# quadrotor_100N_Sheet1.net
KiCad netlist of a schematic drawn in Altium Designer
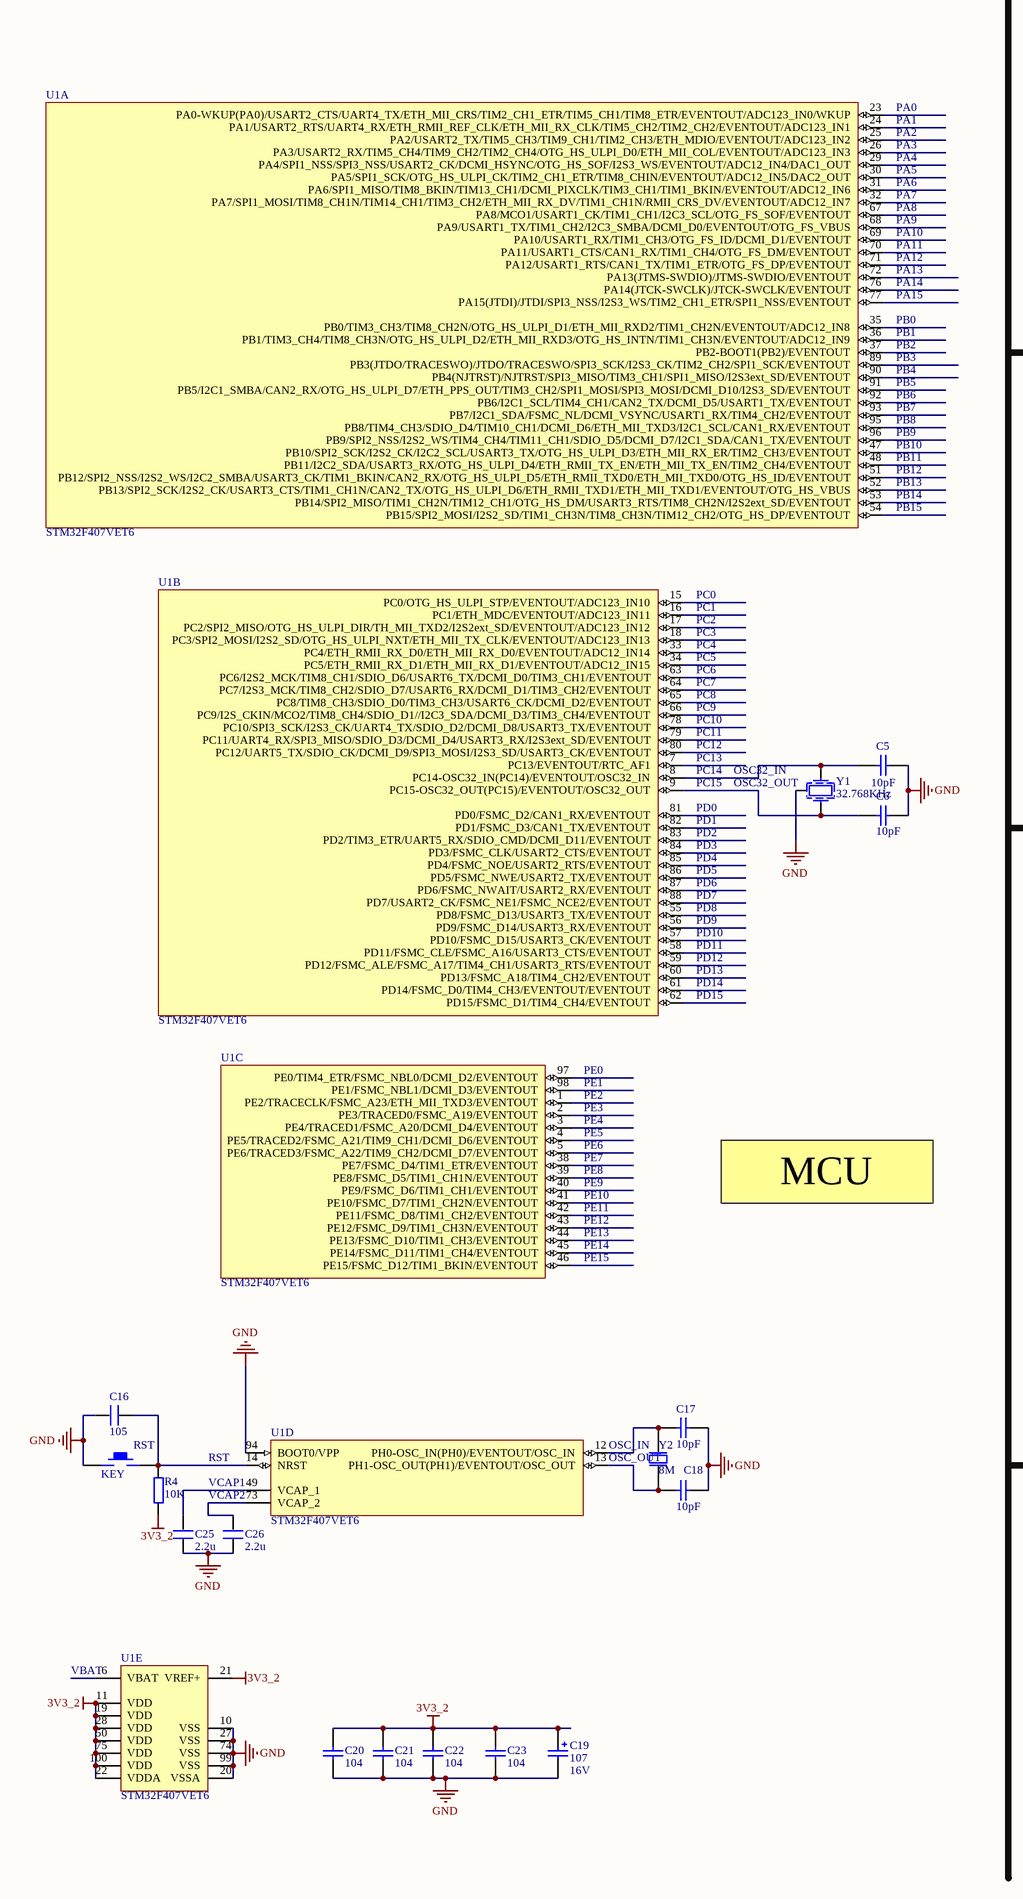
[diagram p0: quadrotor_100N_Sheet1.SchDoc, left]
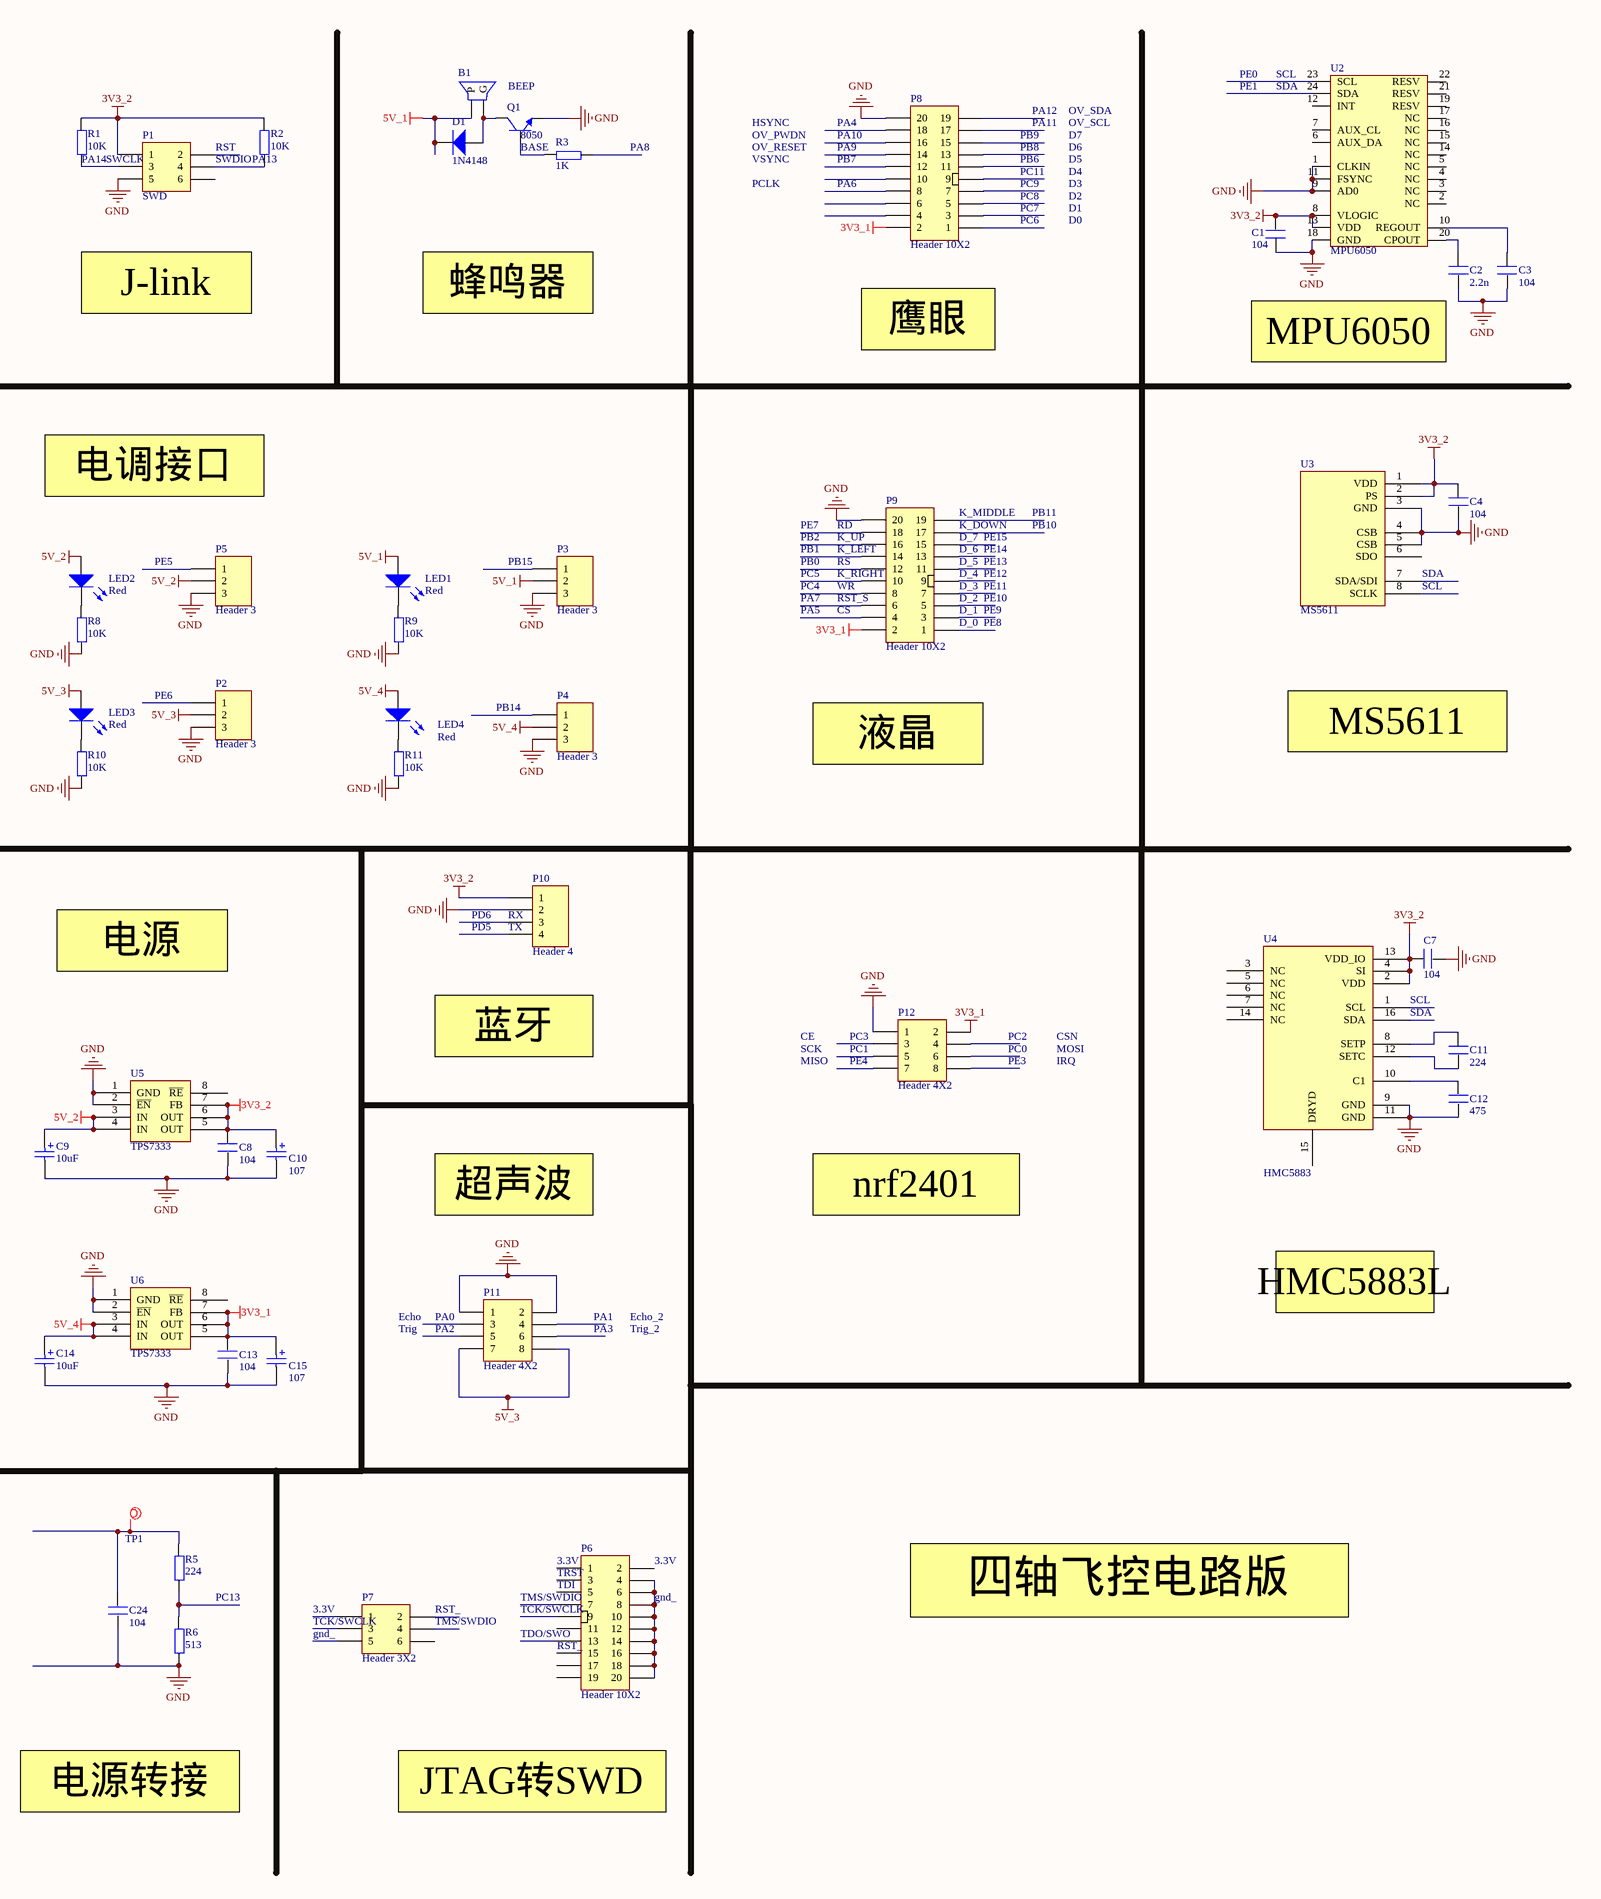
[diagram p1: quadrotor_100N_Sheet1.SchDoc, right]

(export (version "E")
  (design (tool "Eeschema 10.0.6"))
  (components
    (comp (ref "B1") (value "BEEP") (footprint "BEEP") (libsource (lib "电磁组") (part "BEEP")))
    (comp (ref "C1") (value "104") (footprint "C0805") (libsource (lib "WARSHIP") (part "C")))
    (comp (ref "C2") (value "2.2n") (footprint "C0805") (libsource (lib "WARSHIP") (part "C")))
    (comp (ref "C3") (value "104") (footprint "C0805") (libsource (lib "WARSHIP") (part "C")))
    (comp (ref "C4") (value "104") (footprint "C0805") (libsource (lib "WARSHIP") (part "C")))
    (comp (ref "C5")
      (value "10pF")
      (footprint "CAPC2012[0805]")
      (description "Chip Capacitor, PSpice Model")
      (fields
        (field (name "TOLERANCE") "Y5V")
        (field (name "VOLTAGE") "63V")
        (field (name "PUBLISHER") "Altium Limited")
      )
      (libsource (lib "!)Miscellaneous Integrated Library") (part "Cap Chip 1"))
    )
    (comp (ref "C6")
      (value "10pF")
      (footprint "CAPC2012[0805]")
      (description "Chip Capacitor, PSpice Model")
      (fields
        (field (name "TOLERANCE") "Y5V")
        (field (name "VOLTAGE") "63V")
        (field (name "PUBLISHER") "Altium Limited")
      )
      (libsource (lib "!)Miscellaneous Integrated Library") (part "Cap Chip 1"))
    )
    (comp (ref "C7") (value "104") (footprint "C0805") (libsource (lib "WARSHIP") (part "C")))
    (comp (ref "C8") (value "104") (footprint "C0805") (libsource (lib "WARSHIP") (part "C")))
    (comp (ref "C9")
      (value "10uF")
      (footprint "CAPS8")
      (description "Polarized Capacitor (Radial)")
      (fields (field (name "VOLTAGE") "16V") (field (name "PUBLISHER") "Altium Limited"))
      (libsource (lib "!)Miscellaneous Integrated Library") (part "Cap Solid"))
    )
    (comp (ref "C10")
      (value "107")
      (footprint "CAPT6032")
      (description "Molded (Tantalum) Capacitor, 2-Leads,")
      (fields (field (name "VOLTAGE") "16V") (field (name "PUBLISHER") "Altium Limited"))
      (libsource (lib "!)Miscellaneous Integrated Library") (part "Cap Tan"))
    )
    (comp (ref "C11") (value "224") (footprint "C0805") (libsource (lib "WARSHIP") (part "C")))
    (comp (ref "C12") (value "475") (footprint "C0805") (libsource (lib "WARSHIP") (part "C")))
    (comp (ref "C13") (value "104") (footprint "C0805") (libsource (lib "WARSHIP") (part "C")))
    (comp (ref "C14")
      (value "10uF")
      (footprint "CAPS8")
      (description "Polarized Capacitor (Radial)")
      (fields (field (name "VOLTAGE") "16V") (field (name "PUBLISHER") "Altium Limited"))
      (libsource (lib "!)Miscellaneous Integrated Library") (part "Cap Solid"))
    )
    (comp (ref "C15")
      (value "107")
      (footprint "CAPT6032")
      (description "Molded (Tantalum) Capacitor, 2-Leads,")
      (fields (field (name "VOLTAGE") "16V") (field (name "PUBLISHER") "Altium Limited"))
      (libsource (lib "!)Miscellaneous Integrated Library") (part "Cap Tan"))
    )
    (comp (ref "C16") (value "105") (footprint "C0805") (libsource (lib "WARSHIP") (part "C")))
    (comp (ref "C17")
      (value "10pF")
      (footprint "CAPC2012[0805]")
      (description "Chip Capacitor, PSpice Model")
      (fields
        (field (name "TOLERANCE") "Y5V")
        (field (name "VOLTAGE") "63V")
        (field (name "PUBLISHER") "Altium Limited")
      )
      (libsource (lib "!)Miscellaneous Integrated Library") (part "Cap Chip 1"))
    )
    (comp (ref "C18")
      (value "10pF")
      (footprint "CAPC2012[0805]")
      (description "Chip Capacitor, PSpice Model")
      (fields
        (field (name "TOLERANCE") "Y5V")
        (field (name "VOLTAGE") "63V")
        (field (name "PUBLISHER") "Altium Limited")
      )
      (libsource (lib "!)Miscellaneous Integrated Library") (part "Cap Chip 1"))
    )
    (comp (ref "C19")
      (value "107")
      (footprint "CAPT6032")
      (description "Molded (Tantalum) Capacitor, 2-Leads,")
      (fields (field (name "VOLTAGE") "16V") (field (name "PUBLISHER") "Altium Limited"))
      (libsource (lib "!)Miscellaneous Integrated Library") (part "Cap Tan"))
    )
    (comp (ref "C20")
      (value "104")
      (footprint "CAPC2012[0805]")
      (description "Chip Capacitor, PSpice Model")
      (fields
        (field (name "TOLERANCE") "Y5V")
        (field (name "VOLTAGE") "63V")
        (field (name "PUBLISHER") "Altium Limited")
      )
      (libsource (lib "!)Miscellaneous Integrated Library") (part "Cap Chip 1"))
    )
    (comp (ref "C21")
      (value "104")
      (footprint "CAPC2012[0805]")
      (description "Chip Capacitor, PSpice Model")
      (fields
        (field (name "TOLERANCE") "Y5V")
        (field (name "VOLTAGE") "63V")
        (field (name "PUBLISHER") "Altium Limited")
      )
      (libsource (lib "!)Miscellaneous Integrated Library") (part "Cap Chip 1"))
    )
    (comp (ref "C22")
      (value "104")
      (footprint "CAPC2012[0805]")
      (description "Chip Capacitor, PSpice Model")
      (fields
        (field (name "TOLERANCE") "Y5V")
        (field (name "VOLTAGE") "63V")
        (field (name "PUBLISHER") "Altium Limited")
      )
      (libsource (lib "!)Miscellaneous Integrated Library") (part "Cap Chip 1"))
    )
    (comp (ref "C23")
      (value "104")
      (footprint "CAPC2012[0805]")
      (description "Chip Capacitor, PSpice Model")
      (fields
        (field (name "TOLERANCE") "Y5V")
        (field (name "VOLTAGE") "63V")
        (field (name "PUBLISHER") "Altium Limited")
      )
      (libsource (lib "!)Miscellaneous Integrated Library") (part "Cap Chip 1"))
    )
    (comp (ref "C24") (value "104") (footprint "0805C") (libsource (lib "WARSHIP") (part "C")))
    (comp (ref "C25") (value "2.2u") (footprint "C0805") (libsource (lib "WARSHIP") (part "C")))
    (comp (ref "C26") (value "2.2u") (footprint "C0805") (libsource (lib "WARSHIP") (part "C")))
    (comp (ref "D1")
      (value "1N4148")
      (footprint "SOD-80[LL-34]")
      (description "SMT Glass Diode, PSpice Model")
      (fields (field (name "PARTNUMBER") "1N4148") (field (name "PUBLISHER") "Altium Limited"))
      (libsource (lib "!)Miscellaneous Integrated Library") (part "Diode 1N4148"))
    )
    (comp (ref "LED1")
      (value "Red")
      (footprint "LEDC2012(0805)")
      (description "Typical Chip LED")
      (fields (field (name "COLOR") "Red") (field (name "PUBLISHER") "Altium Limited"))
      (libsource (lib "!)Miscellaneous Integrated Library") (part "LED Chip"))
    )
    (comp (ref "LED2")
      (value "Red")
      (footprint "LEDC2012(0805)")
      (description "Typical Chip LED")
      (fields (field (name "COLOR") "Red") (field (name "PUBLISHER") "Altium Limited"))
      (libsource (lib "!)Miscellaneous Integrated Library") (part "LED Chip"))
    )
    (comp (ref "LED3")
      (value "Red")
      (footprint "LEDC2012(0805)")
      (description "Typical Chip LED")
      (fields (field (name "COLOR") "Red") (field (name "PUBLISHER") "Altium Limited"))
      (libsource (lib "!)Miscellaneous Integrated Library") (part "LED Chip"))
    )
    (comp (ref "LED4")
      (value "Red")
      (footprint "LEDC2012(0805)")
      (description "Typical Chip LED")
      (fields (field (name "COLOR") "Red") (field (name "PUBLISHER") "Altium Limited"))
      (libsource (lib "!)Miscellaneous Integrated Library") (part "LED Chip"))
    )
    (comp (ref "P1")
      (value "SWD")
      (footprint "HDR2X3")
      (description "Header, 3-Pin, Dual row")
      (fields (field (name "PUBLISHER") "Altium Limited"))
      (libsource (lib "!)Miscellaneous Integrated Library") (part "Header 3X2"))
    )
    (comp (ref "P2")
      (value "Header 3")
      (footprint "HDR1X3")
      (description "Header, 3-Pin")
      (fields (field (name "PUBLISHER") "Altium Limited"))
      (libsource (lib "!)Miscellaneous Integrated Library") (part "Header 3"))
    )
    (comp (ref "P3")
      (value "Header 3")
      (footprint "HDR1X3")
      (description "Header, 3-Pin")
      (fields (field (name "PUBLISHER") "Altium Limited"))
      (libsource (lib "!)Miscellaneous Integrated Library") (part "Header 3"))
    )
    (comp (ref "P4")
      (value "Header 3")
      (footprint "HDR1X3")
      (description "Header, 3-Pin")
      (fields (field (name "PUBLISHER") "Altium Limited"))
      (libsource (lib "!)Miscellaneous Integrated Library") (part "Header 3"))
    )
    (comp (ref "P5")
      (value "Header 3")
      (footprint "HDR1X3")
      (description "Header, 3-Pin")
      (fields (field (name "PUBLISHER") "Altium Limited"))
      (libsource (lib "!)Miscellaneous Integrated Library") (part "Header 3"))
    )
    (comp (ref "P6")
      (value "Header 10X2")
      (footprint "IDC2.54-20")
      (description "Header, 10-Pin, Dual row")
      (fields (field (name "PUBLISHER") "Altium Limited"))
      (libsource (lib "") (part "Header 10X2_1"))
    )
    (comp (ref "P7")
      (value "Header 3X2")
      (footprint "HDR2X3")
      (description "Header, 3-Pin, Dual row")
      (fields (field (name "PUBLISHER") "Altium Limited"))
      (libsource (lib "!)Miscellaneous Integrated Library") (part "Header 3X2"))
    )
    (comp (ref "P8")
      (value "Header 10X2")
      (footprint "HDR2X10")
      (description "Header, 10-Pin, Dual row")
      (fields (field (name "PUBLISHER") "Altium Limited"))
      (libsource (lib "!)Miscellaneous Integrated Library") (part "Header 10X2"))
    )
    (comp (ref "P9")
      (value "Header 10X2")
      (footprint "HDR2X10")
      (description "Header, 10-Pin, Dual row")
      (fields (field (name "PUBLISHER") "Altium Limited"))
      (libsource (lib "!)Miscellaneous Integrated Library") (part "Header 10X2"))
    )
    (comp (ref "P10")
      (value "Header 4")
      (footprint "HX2.54V-4")
      (description "Header, 4-Pin")
      (fields (field (name "PUBLISHER") "Altium Limited"))
      (libsource (lib "!)Miscellaneous Integrated Library") (part "Header 4"))
    )
    (comp (ref "P11")
      (value "Header 4X2")
      (footprint "HDR2X4")
      (description "Header, 4-Pin, Dual row")
      (fields (field (name "PUBLISHER") "Altium Limited"))
      (libsource (lib "!)Miscellaneous Integrated Library") (part "Header 4X2"))
    )
    (comp (ref "P12")
      (value "Header 4X2")
      (footprint "HDR2X4")
      (description "Header, 4-Pin, Dual row")
      (fields (field (name "PUBLISHER") "Altium Limited"))
      (libsource (lib "!)Miscellaneous Integrated Library") (part "Header 4X2"))
    )
    (comp (ref "Q1")
      (value "8050")
      (footprint "SOT23")
      (description "NPN Bipolar Transistor")
      (fields (field (name "PARTNUMBER") "8050") (field (name "PUBLISHER") "Altium Limited"))
      (libsource (lib "!)Miscellaneous Integrated Library") (part "NPN BC817-40"))
    )
    (comp (ref "R1") (value "10K") (footprint "0805") (libsource (lib "WARSHIP") (part "R")))
    (comp (ref "R2") (value "10K") (footprint "0805") (libsource (lib "WARSHIP") (part "R")))
    (comp (ref "R3") (value "1K") (footprint "0805") (libsource (lib "WARSHIP") (part "R")))
    (comp (ref "R4") (value "10K") (footprint "0805") (libsource (lib "WARSHIP") (part "R")))
    (comp (ref "R5") (value "224") (footprint "0805R") (libsource (lib "WARSHIP") (part "R")))
    (comp (ref "R6") (value "513") (footprint "0805R") (libsource (lib "WARSHIP") (part "R")))
    (comp (ref "R8") (value "10K") (footprint "0805") (libsource (lib "WARSHIP") (part "R")))
    (comp (ref "R9") (value "10K") (footprint "0805") (libsource (lib "WARSHIP") (part "R")))
    (comp (ref "R10") (value "10K") (footprint "0805") (libsource (lib "WARSHIP") (part "R")))
    (comp (ref "R11") (value "10K") (footprint "0805") (libsource (lib "WARSHIP") (part "R")))
    (comp (ref "RST") (value "KEY") (footprint "KEY") (libsource (lib "电磁组") (part "KEY")))
    (comp (ref "TP1")
      (value "Test Point")
      (footprint "TESTPOINT_PAD_3")
      (description "Test Point for Manufature")
      (libsource (lib "!)Miscellaneous Integrated Library") (part "Test Point"))
    )
    (comp (ref "U1")
      (value "STM32F407VET6")
      (footprint "LQFP100_M")
      (libsource (lib "STMicroelectronics STM32 F4") (part "STM32F407VET6"))
    )
    (comp (ref "U2")
      (value "MPU6050")
      (footprint "QFN24")
      (description "9轴运动处理传感器")
      (libsource (lib "ATK-MPU6050六轴传感器模块") (part "MPU6050"))
    )
    (comp (ref "U3") (value "MS5611") (footprint "MS5611") (libsource (lib "电磁组") (part "MS5611")))
    (comp (ref "U4") (value "HMC5883") (footprint "QFN16") (libsource (lib "电磁组") (part "HMC5883")))
    (comp (ref "U5") (value "TPS7333") (footprint "TPS7333") (libsource (lib "Schlib1") (part "TPS7333")))
    (comp (ref "U6") (value "TPS7333") (footprint "TPS7333") (libsource (lib "Schlib1") (part "TPS7333")))
    (comp (ref "Y1")
      (value "32.768KHz")
      (footprint "XTAL")
      (description "3-pin Crystal Oscillator, Case Shelter")
      (libsource (lib "!)Miscellaneous Integrated Library") (part "XTAL 3P"))
    )
    (comp (ref "Y2")
      (value "8M")
      (footprint "XTAL-SMD")
      (description "Crystal Oscillator")
      (fields (field (name "PUBLISHER") "Altium Limited"))
      (libsource (lib "!)Miscellaneous Integrated Library") (part "XTAL"))
    )
  )
  (nets
    (net (code "1") (name "/3.3V") (class "Default")
      (node (ref "P6") (pin "1") (pinfunction "1_1") (pintype "passive"))
      (node (ref "P6") (pin "2") (pinfunction "2_2") (pintype "passive"))
      (node (ref "P7") (pin "1") (pinfunction "1_1") (pintype "passive"))
    )
    (net (code "2") (name "/BASE") (class "Default")
      (node (ref "Q1") (pin "1") (pinfunction "B_1") (pintype "passive"))
      (node (ref "R3") (pin "1") (pintype "passive"))
    )
    (net (code "4") (name "/CS") (class "Default")
      (node (ref "P9") (pin "4") (pinfunction "4_4") (pintype "passive"))
      (node (ref "U1") (pin "30") (pinfunction "PA5/SPI1_SCK/OTG_HS_ULPI_CK/TIM2_CH1_ETR/TIM8_CHIN/EVENTOUT/ADC12_IN5/DAC2_OUT_30") (pintype "bidirectional"))
    )
    (net (code "14") (name "/D_0") (class "Default")
      (node (ref "P9") (pin "1") (pinfunction "1_1") (pintype "passive"))
      (node (ref "U1") (pin "39") (pinfunction "PE8/FSMC_D5/TIM1_CH1N/EVENTOUT_39") (pintype "bidirectional"))
    )
    (net (code "15") (name "/D_1") (class "Default")
      (node (ref "P9") (pin "3") (pinfunction "3_3") (pintype "passive"))
      (node (ref "U1") (pin "40") (pinfunction "PE9/FSMC_D6/TIM1_CH1/EVENTOUT_40") (pintype "bidirectional"))
    )
    (net (code "16") (name "/D_2") (class "Default")
      (node (ref "P9") (pin "5") (pinfunction "5_5") (pintype "passive"))
      (node (ref "U1") (pin "41") (pinfunction "PE10/FSMC_D7/TIM1_CH2N/EVENTOUT_41") (pintype "bidirectional"))
    )
    (net (code "17") (name "/D_3") (class "Default")
      (node (ref "P9") (pin "7") (pinfunction "7_7") (pintype "passive"))
      (node (ref "U1") (pin "42") (pinfunction "PE11/FSMC_D8/TIM1_CH2/EVENTOUT_42") (pintype "bidirectional"))
    )
    (net (code "18") (name "/D_4") (class "Default")
      (node (ref "P9") (pin "9") (pinfunction "9_9") (pintype "passive"))
      (node (ref "U1") (pin "43") (pinfunction "PE12/FSMC_D9/TIM1_CH3N/EVENTOUT_43") (pintype "bidirectional"))
    )
    (net (code "19") (name "/D_5") (class "Default")
      (node (ref "P9") (pin "11") (pinfunction "11_11") (pintype "passive"))
      (node (ref "U1") (pin "44") (pinfunction "PE13/FSMC_D10/TIM1_CH3/EVENTOUT_44") (pintype "bidirectional"))
    )
    (net (code "20") (name "/D_6") (class "Default")
      (node (ref "P9") (pin "13") (pinfunction "13_13") (pintype "passive"))
      (node (ref "U1") (pin "45") (pinfunction "PE14/FSMC_D11/TIM1_CH4/EVENTOUT_45") (pintype "bidirectional"))
    )
    (net (code "21") (name "/D_7") (class "Default")
      (node (ref "P9") (pin "15") (pinfunction "15_15") (pintype "passive"))
      (node (ref "U1") (pin "46") (pinfunction "PE15/FSMC_D12/TIM1_BKIN/EVENTOUT_46") (pintype "bidirectional"))
    )
    (net (code "26") (name "/K_DOWN") (class "Default")
      (node (ref "P9") (pin "17") (pinfunction "17_17") (pintype "passive"))
      (node (ref "U1") (pin "47") (pinfunction "PB10/SPI2_SCK/I2S2_CK/I2C2_SCL/USART3_TX/OTG_HS_ULPI_D3/ETH_MII_RX_ER/TIM2_CH3/EVENTOUT_47") (pintype "bidirectional"))
    )
    (net (code "27") (name "/K_LEFT") (class "Default")
      (node (ref "P9") (pin "14") (pinfunction "14_14") (pintype "passive"))
      (node (ref "U1") (pin "36") (pinfunction "PB1/TIM3_CH4/TIM8_CH3N/OTG_HS_ULPI_D2/ETH_MII_RXD3/OTG_HS_INTN/TIM1_CH3N/EVENTOUT/ADC12_IN9_36") (pintype "bidirectional"))
    )
    (net (code "28") (name "/K_MIDDLE") (class "Default")
      (node (ref "P9") (pin "19") (pinfunction "19_19") (pintype "passive"))
      (node (ref "U1") (pin "48") (pinfunction "PB11/I2C2_SDA/USART3_RX/OTG_HS_ULPI_D4/ETH_RMII_TX_EN/ETH_MII_TX_EN/TIM2_CH4/EVENTOUT_48") (pintype "bidirectional"))
    )
    (net (code "29") (name "/K_RIGHT") (class "Default")
      (node (ref "P9") (pin "10") (pinfunction "10_10") (pintype "passive"))
      (node (ref "U1") (pin "34") (pinfunction "PC5/ETH_RMII_RX_D1/ETH_MII_RX_D1/EVENTOUT/ADC12_IN15_34") (pintype "bidirectional"))
    )
    (net (code "30") (name "/K_UP") (class "Default")
      (node (ref "P9") (pin "16") (pinfunction "16_16") (pintype "passive"))
      (node (ref "U1") (pin "37") (pinfunction "PB2-BOOT1(PB2)/EVENTOUT_37") (pintype "bidirectional"))
    )
    (net (code "33") (name "/OSC32_IN") (class "Default")
      (node (ref "C5") (pin "1") (pinfunction "1_1") (pintype "passive"))
      (node (ref "U1") (pin "8") (pinfunction "PC14-OSC32_IN(PC14)/EVENTOUT/OSC32_IN_8") (pintype "bidirectional"))
      (node (ref "Y1") (pin "1") (pintype "passive"))
    )
    (net (code "34") (name "/OSC32_OUT") (class "Default")
      (node (ref "C6") (pin "1") (pinfunction "1_1") (pintype "passive"))
      (node (ref "U1") (pin "9") (pinfunction "PC15-OSC32_OUT(PC15)/EVENTOUT/OSC32_OUT_9") (pintype "bidirectional"))
      (node (ref "Y1") (pin "2") (pintype "passive"))
    )
    (net (code "35") (name "/OSC_IN") (class "Default")
      (node (ref "C17") (pin "1") (pinfunction "1_1") (pintype "passive"))
      (node (ref "U1") (pin "12") (pinfunction "PH0-OSC_IN(PH0)/EVENTOUT/OSC_IN_12") (pintype "bidirectional"))
      (node (ref "Y2") (pin "2") (pinfunction "OSC2_2") (pintype "passive"))
    )
    (net (code "36") (name "/OSC_OUT") (class "Default")
      (node (ref "C18") (pin "1") (pinfunction "1_1") (pintype "passive"))
      (node (ref "U1") (pin "13") (pinfunction "PH1-OSC_OUT(PH1)/EVENTOUT/OSC_OUT_13") (pintype "bidirectional"))
      (node (ref "Y2") (pin "1") (pinfunction "OSC1_1") (pintype "passive"))
    )
    (net (code "41") (name "/PA0") (class "Default")
      (node (ref "P11") (pin "3") (pinfunction "3_3") (pintype "passive"))
      (node (ref "U1") (pin "23") (pinfunction "PA0-WKUP(PA0)/USART2_CTS/UART4_TX/ETH_MII_CRS/TIM2_CH1_ETR/TIM5_CH1/TIM8_ETR/EVENTOUT/ADC123_IN0/WKUP_23") (pintype "bidirectional"))
    )
    (net (code "42") (name "/PA1") (class "Default")
      (node (ref "P11") (pin "4") (pinfunction "4_4") (pintype "passive"))
      (node (ref "U1") (pin "24") (pinfunction "PA1/USART2_RTS/UART4_RX/ETH_RMII_REF_CLK/ETH_MII_RX_CLK/TIM5_CH2/TIM2_CH2/EVENTOUT/ADC123_IN1_24") (pintype "bidirectional"))
    )
    (net (code "43") (name "/PA2") (class "Default")
      (node (ref "P11") (pin "5") (pinfunction "5_5") (pintype "passive"))
      (node (ref "U1") (pin "25") (pinfunction "PA2/USART2_TX/TIM5_CH3/TIM9_CH1/TIM2_CH3/ETH_MDIO/EVENTOUT/ADC123_IN2_25") (pintype "bidirectional"))
    )
    (net (code "44") (name "/PA3") (class "Default")
      (node (ref "P11") (pin "6") (pinfunction "6_6") (pintype "passive"))
      (node (ref "U1") (pin "26") (pinfunction "PA3/USART2_RX/TIM5_CH4/TIM9_CH2/TIM2_CH4/OTG_HS_ULPI_D0/ETH_MII_COL/EVENTOUT/ADC123_IN3_26") (pintype "bidirectional"))
    )
    (net (code "45") (name "/PA4") (class "Default")
      (node (ref "P8") (pin "18") (pinfunction "18_18") (pintype "passive"))
      (node (ref "U1") (pin "29") (pinfunction "PA4/SPI1_NSS/SPI3_NSS/USART2_CK/DCMI_HSYNC/OTG_HS_SOF/I2S3_WS/EVENTOUT/ADC12_IN4/DAC1_OUT_29") (pintype "bidirectional"))
    )
    (net (code "46") (name "/PA6") (class "Default")
      (node (ref "P8") (pin "8") (pinfunction "8_8") (pintype "passive"))
      (node (ref "U1") (pin "31") (pinfunction "PA6/SPI1_MISO/TIM8_BKIN/TIM13_CH1/DCMI_PIXCLK/TIM3_CH1/TIM1_BKIN/EVENTOUT/ADC12_IN6_31") (pintype "bidirectional"))
    )
    (net (code "47") (name "/PA7") (class "Default")
      (node (ref "P9") (pin "6") (pinfunction "6_6") (pintype "passive"))
      (node (ref "U1") (pin "32") (pinfunction "PA7/SPI1_MOSI/TIM8_CH1N/TIM14_CH1/TIM3_CH2/ETH_MII_RX_DV/TIM1_CH1N/RMII_CRS_DV/EVENTOUT/ADC12_IN7_32") (pintype "bidirectional"))
    )
    (net (code "48") (name "/PA8") (class "Default")
      (node (ref "R3") (pin "2") (pintype "passive"))
      (node (ref "U1") (pin "67") (pinfunction "PA8/MCO1/USART1_CK/TIM1_CH1/I2C3_SCL/OTG_FS_SOF/EVENTOUT_67") (pintype "bidirectional"))
    )
    (net (code "49") (name "/PA9") (class "Default")
      (node (ref "P8") (pin "14") (pinfunction "14_14") (pintype "passive"))
      (node (ref "U1") (pin "68") (pinfunction "PA9/USART1_TX/TIM1_CH2/I2C3_SMBA/DCMI_D0/EVENTOUT/OTG_FS_VBUS_68") (pintype "bidirectional"))
    )
    (net (code "50") (name "/PA10") (class "Default")
      (node (ref "P8") (pin "16") (pinfunction "16_16") (pintype "passive"))
      (node (ref "U1") (pin "69") (pinfunction "PA10/USART1_RX/TIM1_CH3/OTG_FS_ID/DCMI_D1/EVENTOUT_69") (pintype "bidirectional"))
    )
    (net (code "51") (name "/PA11") (class "Default")
      (node (ref "P8") (pin "17") (pinfunction "17_17") (pintype "passive"))
      (node (ref "U1") (pin "70") (pinfunction "PA11/USART1_CTS/CAN1_RX/TIM1_CH4/OTG_FS_DM/EVENTOUT_70") (pintype "bidirectional"))
    )
    (net (code "52") (name "/PA12") (class "Default")
      (node (ref "P8") (pin "19") (pinfunction "19_19") (pintype "passive"))
      (node (ref "U1") (pin "71") (pinfunction "PA12/USART1_RTS/CAN1_TX/TIM1_ETR/OTG_FS_DP/EVENTOUT_71") (pintype "bidirectional"))
    )
    (net (code "53") (name "/PA13") (class "Default")
      (node (ref "P1") (pin "4") (pinfunction "4_4") (pintype "passive"))
      (node (ref "R2") (pin "1") (pintype "passive"))
      (node (ref "U1") (pin "72") (pinfunction "PA13(JTMS-SWDIO)/JTMS-SWDIO/EVENTOUT_72") (pintype "bidirectional"))
    )
    (net (code "54") (name "/PA14") (class "Default")
      (node (ref "P1") (pin "3") (pinfunction "3_3") (pintype "passive"))
      (node (ref "R1") (pin "1") (pintype "passive"))
      (node (ref "U1") (pin "76") (pinfunction "PA14(JTCK-SWCLK)/JTCK-SWCLK/EVENTOUT_76") (pintype "bidirectional"))
    )
    (net (code "55") (name "/PA15") (class "Default")
      (node (ref "U1") (pin "77") (pinfunction "PA15(JTDI)/JTDI/SPI3_NSS/I2S3_WS/TIM2_CH1_ETR/SPI1_NSS/EVENTOUT_77") (pintype "bidirectional"))
    )
    (net (code "56") (name "/PB0") (class "Default")
      (node (ref "P9") (pin "12") (pinfunction "12_12") (pintype "passive"))
      (node (ref "U1") (pin "35") (pinfunction "PB0/TIM3_CH3/TIM8_CH2N/OTG_HS_ULPI_D1/ETH_MII_RXD2/TIM1_CH2N/EVENTOUT/ADC12_IN8_35") (pintype "bidirectional"))
    )
    (net (code "57") (name "/PB3") (class "Default")
      (node (ref "U1") (pin "89") (pinfunction "PB3(JTDO/TRACESWO)/JTDO/TRACESWO/SPI3_SCK/I2S3_CK/TIM2_CH2/SPI1_SCK/EVENTOUT_89") (pintype "bidirectional"))
    )
    (net (code "58") (name "/PB4") (class "Default")
      (node (ref "U1") (pin "90") (pinfunction "PB4(NJTRST)/NJTRST/SPI3_MISO/TIM3_CH1/SPI1_MISO/I2S3ext_SD/EVENTOUT_90") (pintype "bidirectional"))
    )
    (net (code "59") (name "/PB5") (class "Default")
      (node (ref "U1") (pin "91") (pinfunction "PB5/I2C1_SMBA/CAN2_RX/OTG_HS_ULPI_D7/ETH_PPS_OUT/TIM3_CH2/SPI1_MOSI/SPI3_MOSI/DCMI_D10/I2S3_SD/EVENTOUT_91") (pintype "bidirectional"))
    )
    (net (code "60") (name "/PB6") (class "Default")
      (node (ref "P8") (pin "11") (pinfunction "11_11") (pintype "passive"))
      (node (ref "U1") (pin "92") (pinfunction "PB6/I2C1_SCL/TIM4_CH1/CAN2_TX/DCMI_D5/USART1_TX/EVENTOUT_92") (pintype "bidirectional"))
    )
    (net (code "61") (name "/PB7") (class "Default")
      (node (ref "P8") (pin "12") (pinfunction "12_12") (pintype "passive"))
      (node (ref "U1") (pin "93") (pinfunction "PB7/I2C1_SDA/FSMC_NL/DCMI_VSYNC/USART1_RX/TIM4_CH2/EVENTOUT_93") (pintype "bidirectional"))
    )
    (net (code "62") (name "/PB8") (class "Default")
      (node (ref "P8") (pin "13") (pinfunction "13_13") (pintype "passive"))
      (node (ref "U1") (pin "95") (pinfunction "PB8/TIM4_CH3/SDIO_D4/TIM10_CH1/DCMI_D6/ETH_MII_TXD3/I2C1_SCL/CAN1_RX/EVENTOUT_95") (pintype "bidirectional"))
    )
    (net (code "63") (name "/PB9") (class "Default")
      (node (ref "P8") (pin "15") (pinfunction "15_15") (pintype "passive"))
      (node (ref "U1") (pin "96") (pinfunction "PB9/SPI2_NSS/I2S2_WS/TIM4_CH4/TIM11_CH1/SDIO_D5/DCMI_D7/I2C1_SDA/CAN1_TX/EVENTOUT_96") (pintype "bidirectional"))
    )
    (net (code "64") (name "/PB12") (class "Default")
      (node (ref "U1") (pin "51") (pinfunction "PB12/SPI2_NSS/I2S2_WS/I2C2_SMBA/USART3_CK/TIM1_BKIN/CAN2_RX/OTG_HS_ULPI_D5/ETH_RMII_TXD0/ETH_MII_TXD0/OTG_HS_ID/EVENTOUT_51") (pintype "bidirectional"))
    )
    (net (code "65") (name "/PB13") (class "Default")
      (node (ref "U1") (pin "52") (pinfunction "PB13/SPI2_SCK/I2S2_CK/USART3_CTS/TIM1_CH1N/CAN2_TX/OTG_HS_ULPI_D6/ETH_RMII_TXD1/ETH_MII_TXD1/EVENTOUT/OTG_HS_VBUS_52") (pintype "bidirectional"))
    )
    (net (code "66") (name "/PB14") (class "Default")
      (node (ref "P4") (pin "1") (pinfunction "1_1") (pintype "passive"))
      (node (ref "U1") (pin "53") (pinfunction "PB14/SPI2_MISO/TIM1_CH2N/TIM12_CH1/OTG_HS_DM/USART3_RTS/TIM8_CH2N/I2S2ext_SD/EVENTOUT_53") (pintype "bidirectional"))
    )
    (net (code "67") (name "/PB15") (class "Default")
      (node (ref "P3") (pin "1") (pinfunction "1_1") (pintype "passive"))
      (node (ref "U1") (pin "54") (pinfunction "PB15/SPI2_MOSI/I2S2_SD/TIM1_CH3N/TIM8_CH3N/TIM12_CH2/OTG_HS_DP/EVENTOUT_54") (pintype "bidirectional"))
    )
    (net (code "68") (name "/PC0") (class "Default")
      (node (ref "P12") (pin "6") (pinfunction "6_6") (pintype "passive"))
      (node (ref "U1") (pin "15") (pinfunction "PC0/OTG_HS_ULPI_STP/EVENTOUT/ADC123_IN10_15") (pintype "bidirectional"))
    )
    (net (code "69") (name "/PC1") (class "Default")
      (node (ref "P12") (pin "5") (pinfunction "5_5") (pintype "passive"))
      (node (ref "U1") (pin "16") (pinfunction "PC1/ETH_MDC/EVENTOUT/ADC123_IN11_16") (pintype "bidirectional"))
    )
    (net (code "70") (name "/PC2") (class "Default")
      (node (ref "P12") (pin "4") (pinfunction "4_4") (pintype "passive"))
      (node (ref "U1") (pin "17") (pinfunction "PC2/SPI2_MISO/OTG_HS_ULPI_DIR/TH_MII_TXD2/I2S2ext_SD/EVENTOUT/ADC123_IN12_17") (pintype "bidirectional"))
    )
    (net (code "71") (name "/PC3") (class "Default")
      (node (ref "P12") (pin "3") (pinfunction "3_3") (pintype "passive"))
      (node (ref "U1") (pin "18") (pinfunction "PC3/SPI2_MOSI/I2S2_SD/OTG_HS_ULPI_NXT/ETH_MII_TX_CLK/EVENTOUT/ADC123_IN13_18") (pintype "bidirectional"))
    )
    (net (code "72") (name "/PC4") (class "Default")
      (node (ref "P9") (pin "8") (pinfunction "8_8") (pintype "passive"))
      (node (ref "U1") (pin "33") (pinfunction "PC4/ETH_RMII_RX_D0/ETH_MII_RX_D0/EVENTOUT/ADC12_IN14_33") (pintype "bidirectional"))
    )
    (net (code "73") (name "/PC6") (class "Default")
      (node (ref "P8") (pin "1") (pinfunction "1_1") (pintype "passive"))
      (node (ref "U1") (pin "63") (pinfunction "PC6/I2S2_MCK/TIM8_CH1/SDIO_D6/USART6_TX/DCMI_D0/TIM3_CH1/EVENTOUT_63") (pintype "bidirectional"))
    )
    (net (code "74") (name "/PC7") (class "Default")
      (node (ref "P8") (pin "3") (pinfunction "3_3") (pintype "passive"))
      (node (ref "U1") (pin "64") (pinfunction "PC7/I2S3_MCK/TIM8_CH2/SDIO_D7/USART6_RX/DCMI_D1/TIM3_CH2/EVENTOUT_64") (pintype "bidirectional"))
    )
    (net (code "75") (name "/PC8") (class "Default")
      (node (ref "P8") (pin "5") (pinfunction "5_5") (pintype "passive"))
      (node (ref "U1") (pin "65") (pinfunction "PC8/TIM8_CH3/SDIO_D0/TIM3_CH3/USART6_CK/DCMI_D2/EVENTOUT_65") (pintype "bidirectional"))
    )
    (net (code "76") (name "/PC9") (class "Default")
      (node (ref "P8") (pin "7") (pinfunction "7_7") (pintype "passive"))
      (node (ref "U1") (pin "66") (pinfunction "PC9/I2S_CKIN/MCO2/TIM8_CH4/SDIO_D1//I2C3_SDA/DCMI_D3/TIM3_CH4/EVENTOUT_66") (pintype "bidirectional"))
    )
    (net (code "77") (name "/PC10") (class "Default")
      (node (ref "U1") (pin "78") (pinfunction "PC10/SPI3_SCK/I2S3_CK/UART4_TX/SDIO_D2/DCMI_D8/USART3_TX/EVENTOUT_78") (pintype "bidirectional"))
    )
    (net (code "78") (name "/PC11") (class "Default")
      (node (ref "P8") (pin "9") (pinfunction "9_9") (pintype "passive"))
      (node (ref "U1") (pin "79") (pinfunction "PC11/UART4_RX/SPI3_MISO/SDIO_D3/DCMI_D4/USART3_RX/I2S3ext_SD/EVENTOUT_79") (pintype "bidirectional"))
    )
    (net (code "79") (name "/PC12") (class "Default")
      (node (ref "U1") (pin "80") (pinfunction "PC12/UART5_TX/SDIO_CK/DCMI_D9/SPI3_MOSI/I2S3_SD/USART3_CK/EVENTOUT_80") (pintype "bidirectional"))
    )
    (net (code "80") (name "/PC13") (class "Default")
      (node (ref "R5") (pin "1") (pintype "passive"))
      (node (ref "R6") (pin "2") (pintype "passive"))
      (node (ref "U1") (pin "7") (pinfunction "PC13/EVENTOUT/RTC_AF1_7") (pintype "bidirectional"))
    )
    (net (code "82") (name "/PD0") (class "Default")
      (node (ref "U1") (pin "81") (pinfunction "PD0/FSMC_D2/CAN1_RX/EVENTOUT_81") (pintype "bidirectional"))
    )
    (net (code "83") (name "/PD1") (class "Default")
      (node (ref "U1") (pin "82") (pinfunction "PD1/FSMC_D3/CAN1_TX/EVENTOUT_82") (pintype "bidirectional"))
    )
    (net (code "84") (name "/PD2") (class "Default")
      (node (ref "U1") (pin "83") (pinfunction "PD2/TIM3_ETR/UART5_RX/SDIO_CMD/DCMI_D11/EVENTOUT_83") (pintype "bidirectional"))
    )
    (net (code "85") (name "/PD3") (class "Default")
      (node (ref "U1") (pin "84") (pinfunction "PD3/FSMC_CLK/USART2_CTS/EVENTOUT_84") (pintype "bidirectional"))
    )
    (net (code "86") (name "/PD4") (class "Default")
      (node (ref "U1") (pin "85") (pinfunction "PD4/FSMC_NOE/USART2_RTS/EVENTOUT_85") (pintype "bidirectional"))
    )
    (net (code "87") (name "/PD5") (class "Default")
      (node (ref "P10") (pin "4") (pinfunction "4_4") (pintype "passive"))
      (node (ref "U1") (pin "86") (pinfunction "PD5/FSMC_NWE/USART2_TX/EVENTOUT_86") (pintype "bidirectional"))
    )
    (net (code "88") (name "/PD6") (class "Default")
      (node (ref "P10") (pin "3") (pinfunction "3_3") (pintype "passive"))
      (node (ref "U1") (pin "87") (pinfunction "PD6/FSMC_NWAIT/USART2_RX/EVENTOUT_87") (pintype "bidirectional"))
    )
    (net (code "89") (name "/PD7") (class "Default")
      (node (ref "U1") (pin "88") (pinfunction "PD7/USART2_CK/FSMC_NE1/FSMC_NCE2/EVENTOUT_88") (pintype "bidirectional"))
    )
    (net (code "90") (name "/PD8") (class "Default")
      (node (ref "U1") (pin "55") (pinfunction "PD8/FSMC_D13/USART3_TX/EVENTOUT_55") (pintype "bidirectional"))
    )
    (net (code "91") (name "/PD9") (class "Default")
      (node (ref "U1") (pin "56") (pinfunction "PD9/FSMC_D14/USART3_RX/EVENTOUT_56") (pintype "bidirectional"))
    )
    (net (code "92") (name "/PD10") (class "Default")
      (node (ref "U1") (pin "57") (pinfunction "PD10/FSMC_D15/USART3_CK/EVENTOUT_57") (pintype "bidirectional"))
    )
    (net (code "93") (name "/PD11") (class "Default")
      (node (ref "U1") (pin "58") (pinfunction "PD11/FSMC_CLE/FSMC_A16/USART3_CTS/EVENTOUT_58") (pintype "bidirectional"))
    )
    (net (code "94") (name "/PD12") (class "Default")
      (node (ref "U1") (pin "59") (pinfunction "PD12/FSMC_ALE/FSMC_A17/TIM4_CH1/USART3_RTS/EVENTOUT_59") (pintype "bidirectional"))
    )
    (net (code "95") (name "/PD13") (class "Default")
      (node (ref "U1") (pin "60") (pinfunction "PD13/FSMC_A18/TIM4_CH2/EVENTOUT_60") (pintype "bidirectional"))
    )
    (net (code "96") (name "/PD14") (class "Default")
      (node (ref "U1") (pin "61") (pinfunction "PD14/FSMC_D0/TIM4_CH3/EVENTOUT/EVENTOUT_61") (pintype "bidirectional"))
    )
    (net (code "97") (name "/PD15") (class "Default")
      (node (ref "U1") (pin "62") (pinfunction "PD15/FSMC_D1/TIM4_CH4/EVENTOUT_62") (pintype "bidirectional"))
    )
    (net (code "98") (name "/PE0") (class "Default")
      (node (ref "U1") (pin "97") (pinfunction "PE0/TIM4_ETR/FSMC_NBL0/DCMI_D2/EVENTOUT_97") (pintype "bidirectional"))
      (node (ref "U2") (pin "23") (pinfunction "SCL_23") (pintype "passive"))
      (node (ref "U3") (pin "8") (pinfunction "SCLK_8") (pintype "passive"))
      (node (ref "U4") (pin "1") (pinfunction "SCL_1") (pintype "passive"))
    )
    (net (code "99") (name "/PE1") (class "Default")
      (node (ref "U1") (pin "98") (pinfunction "PE1/FSMC_NBL1/DCMI_D3/EVENTOUT_98") (pintype "bidirectional"))
      (node (ref "U2") (pin "24") (pinfunction "SDA_24") (pintype "passive"))
      (node (ref "U3") (pin "7") (pinfunction "SDA/SDI_7") (pintype "passive"))
      (node (ref "U4") (pin "16") (pinfunction "SDA_16") (pintype "passive"))
    )
    (net (code "100") (name "/PE2") (class "Default")
      (node (ref "U1") (pin "1") (pinfunction "PE2/TRACECLK/FSMC_A23/ETH_MII_TXD3/EVENTOUT_1") (pintype "bidirectional"))
    )
    (net (code "101") (name "/PE3") (class "Default")
      (node (ref "P12") (pin "8") (pinfunction "8_8") (pintype "passive"))
      (node (ref "U1") (pin "2") (pinfunction "PE3/TRACED0/FSMC_A19/EVENTOUT_2") (pintype "bidirectional"))
    )
    (net (code "102") (name "/PE4") (class "Default")
      (node (ref "P12") (pin "7") (pinfunction "7_7") (pintype "passive"))
      (node (ref "U1") (pin "3") (pinfunction "PE4/TRACED1/FSMC_A20/DCMI_D4/EVENTOUT_3") (pintype "bidirectional"))
    )
    (net (code "103") (name "/PE5") (class "Default")
      (node (ref "P5") (pin "1") (pinfunction "1_1") (pintype "passive"))
      (node (ref "U1") (pin "4") (pinfunction "PE5/TRACED2/FSMC_A21/TIM9_CH1/DCMI_D6/EVENTOUT_4") (pintype "bidirectional"))
    )
    (net (code "104") (name "/PE6") (class "Default")
      (node (ref "P2") (pin "1") (pinfunction "1_1") (pintype "passive"))
      (node (ref "U1") (pin "5") (pinfunction "PE6/TRACED3/FSMC_A22/TIM9_CH2/DCMI_D7/EVENTOUT_5") (pintype "bidirectional"))
    )
    (net (code "105") (name "/PE7") (class "Default")
      (node (ref "P9") (pin "18") (pinfunction "18_18") (pintype "passive"))
      (node (ref "U1") (pin "38") (pinfunction "PE7/FSMC_D4/TIM1_ETR/EVENTOUT_38") (pintype "bidirectional"))
    )
    (net (code "106") (name "/RST") (class "Default")
      (node (ref "C16") (pin "2") (pintype "passive"))
      (node (ref "P1") (pin "2") (pinfunction "2_2") (pintype "passive"))
      (node (ref "R4") (pin "2") (pintype "passive"))
      (node (ref "RST") (pin "2") (pinfunction "2_2") (pintype "passive"))
      (node (ref "U1") (pin "14") (pinfunction "NRST_14") (pintype "bidirectional"))
    )
    (net (code "107") (name "/RST_") (class "Default")
      (node (ref "P6") (pin "15") (pinfunction "15_15") (pintype "passive"))
      (node (ref "P7") (pin "2") (pinfunction "2_2") (pintype "passive"))
    )
    (net (code "109") (name "/TCK{slash}SWCLK") (class "Default")
      (node (ref "P6") (pin "9") (pinfunction "9_9") (pintype "passive"))
      (node (ref "P7") (pin "3") (pinfunction "3_3") (pintype "passive"))
    )
    (net (code "110") (name "/TDI") (class "Default")
      (node (ref "P6") (pin "5") (pinfunction "5_5") (pintype "passive"))
    )
    (net (code "111") (name "/TDO{slash}SWO") (class "Default")
      (node (ref "P6") (pin "13") (pinfunction "13_13") (pintype "passive"))
    )
    (net (code "112") (name "/TMS{slash}SWDIO") (class "Default")
      (node (ref "P6") (pin "7") (pinfunction "7_7") (pintype "passive"))
      (node (ref "P7") (pin "4") (pinfunction "4_4") (pintype "passive"))
    )
    (net (code "113") (name "/TRST") (class "Default")
      (node (ref "P6") (pin "3") (pinfunction "3_3") (pintype "passive"))
    )
    (net (code "116") (name "/VBAT") (class "Default")
      (node (ref "U1") (pin "6") (pinfunction "VBAT_6") (pintype "power_in"))
    )
    (net (code "117") (name "/VCAP1") (class "Default")
      (node (ref "C25") (pin "2") (pintype "passive"))
      (node (ref "U1") (pin "49") (pinfunction "VCAP_1_49") (pintype "power_in"))
    )
    (net (code "118") (name "/VCAP2") (class "Default")
      (node (ref "C26") (pin "2") (pintype "passive"))
      (node (ref "U1") (pin "73") (pinfunction "VCAP_2_73") (pintype "power_in"))
    )
    (net (code "120") (name "/gnd_") (class "Default")
      (node (ref "P6") (pin "10") (pinfunction "10_10") (pintype "passive"))
      (node (ref "P6") (pin "12") (pinfunction "12_12") (pintype "passive"))
      (node (ref "P6") (pin "14") (pinfunction "14_14") (pintype "passive"))
      (node (ref "P6") (pin "16") (pinfunction "16_16") (pintype "passive"))
      (node (ref "P6") (pin "18") (pinfunction "18_18") (pintype "passive"))
      (node (ref "P6") (pin "20") (pinfunction "20_20") (pintype "passive"))
      (node (ref "P6") (pin "4") (pinfunction "4_4") (pintype "passive"))
      (node (ref "P6") (pin "6") (pinfunction "6_6") (pintype "passive"))
      (node (ref "P6") (pin "8") (pinfunction "8_8") (pintype "passive"))
      (node (ref "P7") (pin "5") (pinfunction "5_5") (pintype "passive"))
    )
    (net (code "121") (name "3V3_1") (class "Default")
      (node (ref "C13") (pin "2") (pintype "passive"))
      (node (ref "C15") (pin "1") (pinfunction "1_1") (pintype "passive"))
      (node (ref "P12") (pin "2") (pinfunction "2_2") (pintype "passive"))
      (node (ref "P8") (pin "2") (pinfunction "2_2") (pintype "passive"))
      (node (ref "P9") (pin "2") (pinfunction "2_2") (pintype "passive"))
      (node (ref "U6") (pin "5") (pinfunction "OUT_5") (pintype "passive"))
      (node (ref "U6") (pin "6") (pinfunction "OUT_6") (pintype "passive"))
      (node (ref "U6") (pin "7") (pinfunction "FB_7") (pintype "passive"))
    )
    (net (code "122") (name "3V3_2") (class "Default")
      (node (ref "C1") (pin "1") (pintype "passive"))
      (node (ref "C10") (pin "1") (pinfunction "1_1") (pintype "passive"))
      (node (ref "C19") (pin "1") (pinfunction "1_1") (pintype "passive"))
      (node (ref "C20") (pin "2") (pinfunction "2_2") (pintype "passive"))
      (node (ref "C21") (pin "2") (pinfunction "2_2") (pintype "passive"))
      (node (ref "C22") (pin "2") (pinfunction "2_2") (pintype "passive"))
      (node (ref "C23") (pin "2") (pinfunction "2_2") (pintype "passive"))
      (node (ref "C4") (pin "2") (pintype "passive"))
      (node (ref "C7") (pin "1") (pintype "passive"))
      (node (ref "C8") (pin "2") (pintype "passive"))
      (node (ref "P1") (pin "1") (pinfunction "1_1") (pintype "passive"))
      (node (ref "P10") (pin "1") (pinfunction "1_1") (pintype "passive"))
      (node (ref "R1") (pin "2") (pintype "passive"))
      (node (ref "R2") (pin "2") (pintype "passive"))
      (node (ref "R4") (pin "1") (pintype "passive"))
      (node (ref "U1") (pin "100") (pinfunction "VDD_100") (pintype "power_in"))
      (node (ref "U1") (pin "11") (pinfunction "VDD_11") (pintype "power_in"))
      (node (ref "U1") (pin "19") (pinfunction "VDD_19") (pintype "power_in"))
      (node (ref "U1") (pin "21") (pinfunction "VREF+_21") (pintype "power_in"))
      (node (ref "U1") (pin "22") (pinfunction "VDDA_22") (pintype "power_in"))
      (node (ref "U1") (pin "28") (pinfunction "VDD_28") (pintype "power_in"))
      (node (ref "U1") (pin "50") (pinfunction "VDD_50") (pintype "power_in"))
      (node (ref "U1") (pin "75") (pinfunction "VDD_75") (pintype "power_in"))
      (node (ref "U2") (pin "13") (pinfunction "VDD_13") (pintype "passive"))
      (node (ref "U2") (pin "8") (pinfunction "VLOGIC_8") (pintype "passive"))
      (node (ref "U3") (pin "1") (pinfunction "VDD_1") (pintype "passive"))
      (node (ref "U3") (pin "2") (pinfunction "PS_2") (pintype "passive"))
      (node (ref "U4") (pin "13") (pinfunction "VDD_IO_13") (pintype "passive"))
      (node (ref "U4") (pin "2") (pinfunction "VDD_2") (pintype "passive"))
      (node (ref "U4") (pin "4") (pinfunction "SI_4") (pintype "passive"))
      (node (ref "U5") (pin "5") (pinfunction "OUT_5") (pintype "passive"))
      (node (ref "U5") (pin "6") (pinfunction "OUT_6") (pintype "passive"))
      (node (ref "U5") (pin "7") (pinfunction "FB_7") (pintype "passive"))
    )
    (net (code "123") (name "5V_1") (class "Default")
      (node (ref "B1") (pin "1") (pinfunction "P_1") (pintype "passive"))
      (node (ref "D1") (pin "K") (pinfunction "K_K") (pintype "passive"))
      (node (ref "LED1") (pin "A") (pinfunction "A_A") (pintype "passive"))
      (node (ref "P3") (pin "2") (pinfunction "2_2") (pintype "passive"))
    )
    (net (code "124") (name "5V_2") (class "Default")
      (node (ref "C9") (pin "1") (pinfunction "1_1") (pintype "passive"))
      (node (ref "LED2") (pin "A") (pinfunction "A_A") (pintype "passive"))
      (node (ref "P5") (pin "2") (pinfunction "2_2") (pintype "passive"))
      (node (ref "U5") (pin "3") (pinfunction "IN_3") (pintype "passive"))
      (node (ref "U5") (pin "4") (pinfunction "IN_4") (pintype "passive"))
    )
    (net (code "125") (name "5V_3") (class "Default")
      (node (ref "LED3") (pin "A") (pinfunction "A_A") (pintype "passive"))
      (node (ref "P11") (pin "7") (pinfunction "7_7") (pintype "passive"))
      (node (ref "P11") (pin "8") (pinfunction "8_8") (pintype "passive"))
      (node (ref "P2") (pin "2") (pinfunction "2_2") (pintype "passive"))
    )
    (net (code "126") (name "5V_4") (class "Default")
      (node (ref "C14") (pin "1") (pinfunction "1_1") (pintype "passive"))
      (node (ref "LED4") (pin "A") (pinfunction "A_A") (pintype "passive"))
      (node (ref "P4") (pin "2") (pinfunction "2_2") (pintype "passive"))
      (node (ref "U6") (pin "3") (pinfunction "IN_3") (pintype "passive"))
      (node (ref "U6") (pin "4") (pinfunction "IN_4") (pintype "passive"))
    )
    (net (code "127") (name "GND") (class "Default")
      (node (ref "C1") (pin "2") (pintype "passive"))
      (node (ref "C10") (pin "2") (pinfunction "2_2") (pintype "passive"))
      (node (ref "C12") (pin "1") (pintype "passive"))
      (node (ref "C13") (pin "1") (pintype "passive"))
      (node (ref "C14") (pin "2") (pinfunction "2_2") (pintype "passive"))
      (node (ref "C15") (pin "2") (pinfunction "2_2") (pintype "passive"))
      (node (ref "C16") (pin "1") (pintype "passive"))
      (node (ref "C17") (pin "2") (pinfunction "2_2") (pintype "passive"))
      (node (ref "C18") (pin "2") (pinfunction "2_2") (pintype "passive"))
      (node (ref "C19") (pin "2") (pinfunction "2_2") (pintype "passive"))
      (node (ref "C2") (pin "1") (pintype "passive"))
      (node (ref "C20") (pin "1") (pinfunction "1_1") (pintype "passive"))
      (node (ref "C21") (pin "1") (pinfunction "1_1") (pintype "passive"))
      (node (ref "C22") (pin "1") (pinfunction "1_1") (pintype "passive"))
      (node (ref "C23") (pin "1") (pinfunction "1_1") (pintype "passive"))
      (node (ref "C24") (pin "1") (pintype "passive"))
      (node (ref "C25") (pin "1") (pintype "passive"))
      (node (ref "C26") (pin "1") (pintype "passive"))
      (node (ref "C3") (pin "1") (pintype "passive"))
      (node (ref "C4") (pin "1") (pintype "passive"))
      (node (ref "C5") (pin "2") (pinfunction "2_2") (pintype "passive"))
      (node (ref "C6") (pin "2") (pinfunction "2_2") (pintype "passive"))
      (node (ref "C7") (pin "2") (pintype "passive"))
      (node (ref "C8") (pin "1") (pintype "passive"))
      (node (ref "C9") (pin "2") (pinfunction "2_2") (pintype "passive"))
      (node (ref "P1") (pin "5") (pinfunction "5_5") (pintype "passive"))
      (node (ref "P10") (pin "2") (pinfunction "2_2") (pintype "passive"))
      (node (ref "P11") (pin "1") (pinfunction "1_1") (pintype "passive"))
      (node (ref "P11") (pin "2") (pinfunction "2_2") (pintype "passive"))
      (node (ref "P12") (pin "1") (pinfunction "1_1") (pintype "passive"))
      (node (ref "P2") (pin "3") (pinfunction "3_3") (pintype "passive"))
      (node (ref "P3") (pin "3") (pinfunction "3_3") (pintype "passive"))
      (node (ref "P4") (pin "3") (pinfunction "3_3") (pintype "passive"))
      (node (ref "P5") (pin "3") (pinfunction "3_3") (pintype "passive"))
      (node (ref "P8") (pin "20") (pinfunction "20_20") (pintype "passive"))
      (node (ref "P9") (pin "20") (pinfunction "20_20") (pintype "passive"))
      (node (ref "Q1") (pin "2") (pinfunction "E_2") (pintype "passive"))
      (node (ref "R10") (pin "1") (pintype "passive"))
      (node (ref "R11") (pin "1") (pintype "passive"))
      (node (ref "R6") (pin "1") (pintype "passive"))
      (node (ref "R8") (pin "1") (pintype "passive"))
      (node (ref "R9") (pin "1") (pintype "passive"))
      (node (ref "RST") (pin "1") (pinfunction "1_1") (pintype "passive"))
      (node (ref "U1") (pin "10") (pinfunction "VSS_10") (pintype "power_in"))
      (node (ref "U1") (pin "20") (pinfunction "VSSA_20") (pintype "power_in"))
      (node (ref "U1") (pin "27") (pinfunction "VSS_27") (pintype "power_in"))
      (node (ref "U1") (pin "74") (pinfunction "VSS_74") (pintype "power_in"))
      (node (ref "U1") (pin "94") (pinfunction "BOOT0/VPP_94") (pintype "input"))
      (node (ref "U1") (pin "99") (pinfunction "VSS_99") (pintype "power_in"))
      (node (ref "U2") (pin "1") (pinfunction "CLKIN_1") (pintype "passive"))
      (node (ref "U2") (pin "11") (pinfunction "FSYNC_11") (pintype "passive"))
      (node (ref "U2") (pin "18") (pinfunction "GND_18") (pintype "passive"))
      (node (ref "U2") (pin "9") (pinfunction "AD0_9") (pintype "passive"))
      (node (ref "U3") (pin "3") (pinfunction "GND_3") (pintype "passive"))
      (node (ref "U3") (pin "4") (pinfunction "CSB_4") (pintype "passive"))
      (node (ref "U3") (pin "5") (pinfunction "CSB_5") (pintype "passive"))
      (node (ref "U4") (pin "11") (pinfunction "GND_11") (pintype "passive"))
      (node (ref "U4") (pin "9") (pinfunction "GND_9") (pintype "passive"))
      (node (ref "U5") (pin "1") (pinfunction "GND_1") (pintype "passive"))
      (node (ref "U5") (pin "2") (pinfunction "~{EN}_2") (pintype "passive"))
      (node (ref "U6") (pin "1") (pinfunction "GND_1") (pintype "passive"))
      (node (ref "U6") (pin "2") (pinfunction "~{EN}_2") (pintype "passive"))
      (node (ref "Y1") (pin "3") (pintype "passive"))
    )
    (net (code "128") (name "Net-(B1-G)") (class "Default")
      (node (ref "B1") (pin "2") (pinfunction "G_2") (pintype "passive"))
      (node (ref "D1") (pin "A") (pinfunction "A_A") (pintype "passive"))
      (node (ref "Q1") (pin "3") (pinfunction "C_3") (pintype "passive"))
    )
    (net (code "129") (name "Net-(LED1-PadC)") (class "Default")
      (node (ref "LED1") (pin "C") (pinfunction "C_C") (pintype "passive"))
      (node (ref "R9") (pin "2") (pintype "passive"))
    )
    (net (code "130") (name "Net-(LED2-PadC)") (class "Default")
      (node (ref "LED2") (pin "C") (pinfunction "C_C") (pintype "passive"))
      (node (ref "R8") (pin "2") (pintype "passive"))
    )
    (net (code "131") (name "Net-(LED3-PadC)") (class "Default")
      (node (ref "LED3") (pin "C") (pinfunction "C_C") (pintype "passive"))
      (node (ref "R10") (pin "2") (pintype "passive"))
    )
    (net (code "132") (name "Net-(LED4-PadC)") (class "Default")
      (node (ref "LED4") (pin "C") (pinfunction "C_C") (pintype "passive"))
      (node (ref "R11") (pin "2") (pintype "passive"))
    )
    (net (code "133") (name "Net-(TP1-TP)") (class "Default")
      (node (ref "C24") (pin "2") (pintype "passive"))
      (node (ref "R5") (pin "2") (pintype "passive"))
      (node (ref "TP1") (pin "1") (pinfunction "TP_1") (pintype "passive"))
    )
    (net (code "134") (name "Net-(U2-CPOUT)") (class "Default")
      (node (ref "C2") (pin "2") (pintype "passive"))
      (node (ref "U2") (pin "20") (pinfunction "CPOUT_20") (pintype "passive"))
    )
    (net (code "135") (name "Net-(U2-REGOUT)") (class "Default")
      (node (ref "C3") (pin "2") (pintype "passive"))
      (node (ref "U2") (pin "10") (pinfunction "REGOUT_10") (pintype "passive"))
    )
    (net (code "136") (name "Net-(U4-C1)") (class "Default")
      (node (ref "C12") (pin "2") (pintype "passive"))
      (node (ref "U4") (pin "10") (pinfunction "C1_10") (pintype "passive"))
    )
    (net (code "137") (name "Net-(U4-SETC)") (class "Default")
      (node (ref "C11") (pin "1") (pintype "passive"))
      (node (ref "U4") (pin "12") (pinfunction "SETC_12") (pintype "passive"))
    )
    (net (code "138") (name "Net-(U4-SETP)") (class "Default")
      (node (ref "C11") (pin "2") (pintype "passive"))
      (node (ref "U4") (pin "8") (pinfunction "SETP_8") (pintype "passive"))
    )
    (net (code "139") (name "unconnected-(P1-Pad6)") (class "Default")
      (node (ref "P1") (pin "6") (pinfunction "6_6") (pintype "passive"))
    )
    (net (code "140") (name "unconnected-(P6-Pad11)") (class "Default")
      (node (ref "P6") (pin "11") (pinfunction "11_11") (pintype "passive"))
    )
    (net (code "141") (name "unconnected-(P6-Pad17)") (class "Default")
      (node (ref "P6") (pin "17") (pinfunction "17_17") (pintype "passive"))
    )
    (net (code "142") (name "unconnected-(P6-Pad19)") (class "Default")
      (node (ref "P6") (pin "19") (pinfunction "19_19") (pintype "passive"))
    )
    (net (code "143") (name "unconnected-(P7-Pad6)") (class "Default")
      (node (ref "P7") (pin "6") (pinfunction "6_6") (pintype "passive"))
    )
    (net (code "144") (name "unconnected-(P8-Pad4)") (class "Default")
      (node (ref "P8") (pin "4") (pinfunction "4_4") (pintype "passive"))
    )
    (net (code "145") (name "unconnected-(P8-Pad6)") (class "Default")
      (node (ref "P8") (pin "6") (pinfunction "6_6") (pintype "passive"))
    )
    (net (code "146") (name "unconnected-(P8-Pad10)") (class "Default")
      (node (ref "P8") (pin "10") (pinfunction "10_10") (pintype "passive"))
    )
    (net (code "147") (name "unconnected-(U2-AUX_CL-Pad7)") (class "Default")
      (node (ref "U2") (pin "7") (pinfunction "AUX_CL_7") (pintype "passive"))
    )
    (net (code "148") (name "unconnected-(U2-AUX_DA-Pad6)") (class "Default")
      (node (ref "U2") (pin "6") (pinfunction "AUX_DA_6") (pintype "passive"))
    )
    (net (code "149") (name "unconnected-(U2-INT-Pad12)") (class "Default")
      (node (ref "U2") (pin "12") (pinfunction "INT_12") (pintype "passive"))
    )
    (net (code "150") (name "unconnected-(U2-NC-Pad2)") (class "Default")
      (node (ref "U2") (pin "2") (pinfunction "NC_2") (pintype "passive"))
    )
    (net (code "151") (name "unconnected-(U2-NC-Pad3)") (class "Default")
      (node (ref "U2") (pin "3") (pinfunction "NC_3") (pintype "passive"))
    )
    (net (code "152") (name "unconnected-(U2-NC-Pad4)") (class "Default")
      (node (ref "U2") (pin "4") (pinfunction "NC_4") (pintype "passive"))
    )
    (net (code "153") (name "unconnected-(U2-NC-Pad5)") (class "Default")
      (node (ref "U2") (pin "5") (pinfunction "NC_5") (pintype "passive"))
    )
    (net (code "154") (name "unconnected-(U2-NC-Pad14)") (class "Default")
      (node (ref "U2") (pin "14") (pinfunction "NC_14") (pintype "passive"))
    )
    (net (code "155") (name "unconnected-(U2-NC-Pad15)") (class "Default")
      (node (ref "U2") (pin "15") (pinfunction "NC_15") (pintype "passive"))
    )
    (net (code "156") (name "unconnected-(U2-NC-Pad16)") (class "Default")
      (node (ref "U2") (pin "16") (pinfunction "NC_16") (pintype "passive"))
    )
    (net (code "157") (name "unconnected-(U2-NC-Pad17)") (class "Default")
      (node (ref "U2") (pin "17") (pinfunction "NC_17") (pintype "passive"))
    )
    (net (code "158") (name "unconnected-(U2-RESV-Pad19)") (class "Default")
      (node (ref "U2") (pin "19") (pinfunction "RESV_19") (pintype "passive"))
    )
    (net (code "159") (name "unconnected-(U2-RESV-Pad21)") (class "Default")
      (node (ref "U2") (pin "21") (pinfunction "RESV_21") (pintype "passive"))
    )
    (net (code "160") (name "unconnected-(U2-RESV-Pad22)") (class "Default")
      (node (ref "U2") (pin "22") (pinfunction "RESV_22") (pintype "passive"))
    )
    (net (code "161") (name "unconnected-(U3-SDO-Pad6)") (class "Default")
      (node (ref "U3") (pin "6") (pinfunction "SDO_6") (pintype "passive"))
    )
    (net (code "162") (name "unconnected-(U4-DRYD-Pad15)") (class "Default")
      (node (ref "U4") (pin "15") (pinfunction "DRYD_15") (pintype "passive"))
    )
    (net (code "163") (name "unconnected-(U4-NC-Pad3)") (class "Default")
      (node (ref "U4") (pin "3") (pinfunction "NC_3") (pintype "passive"))
    )
    (net (code "164") (name "unconnected-(U4-NC-Pad5)") (class "Default")
      (node (ref "U4") (pin "5") (pinfunction "NC_5") (pintype "passive"))
    )
    (net (code "165") (name "unconnected-(U4-NC-Pad6)") (class "Default")
      (node (ref "U4") (pin "6") (pinfunction "NC_6") (pintype "passive"))
    )
    (net (code "166") (name "unconnected-(U4-NC-Pad7)") (class "Default")
      (node (ref "U4") (pin "7") (pinfunction "NC_7") (pintype "passive"))
    )
    (net (code "167") (name "unconnected-(U4-NC-Pad14)") (class "Default")
      (node (ref "U4") (pin "14") (pinfunction "NC_14") (pintype "passive"))
    )
    (net (code "168") (name "unconnected-(U5-~{RE}-Pad8)") (class "Default")
      (node (ref "U5") (pin "8") (pinfunction "~{RE}_8") (pintype "passive"))
    )
    (net (code "169") (name "unconnected-(U6-~{RE}-Pad8)") (class "Default")
      (node (ref "U6") (pin "8") (pinfunction "~{RE}_8") (pintype "passive"))
    )
  )
)
